# Main.net
KiCad netlist of a schematic drawn in Altium Designer
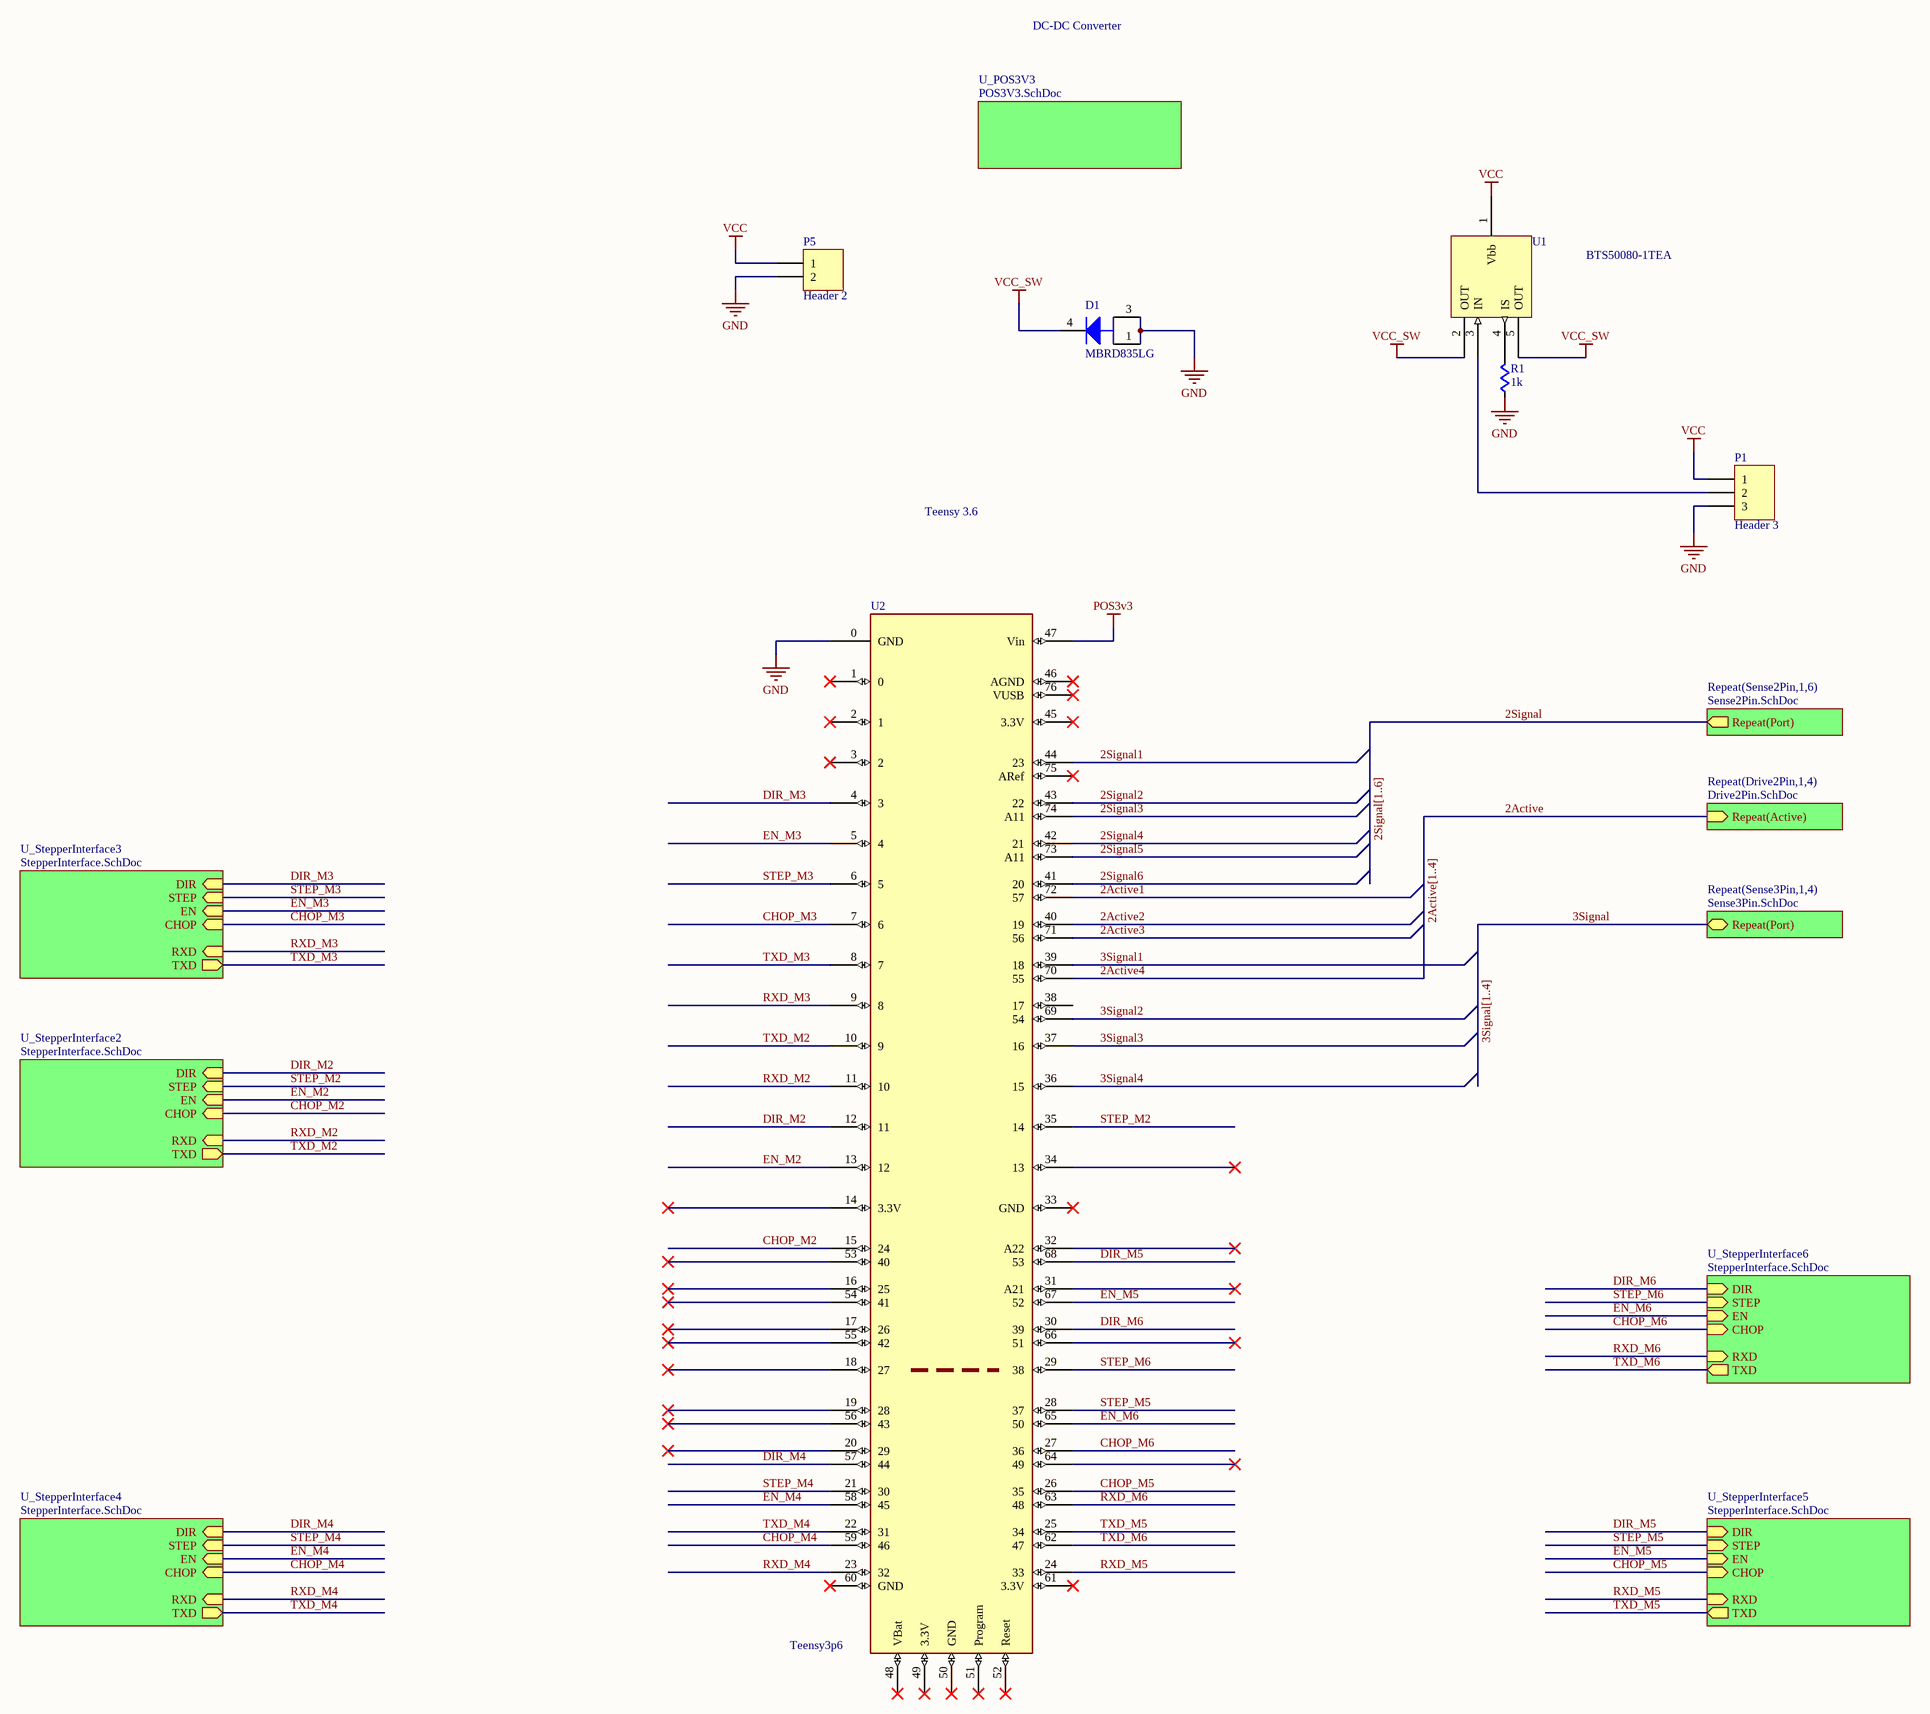
[diagram p0: Main.SchDoc]

(export (version "E")
  (design (tool "Eeschema 10.0.6"))
  (components
    (comp (ref "D1")
      (value "MBRD835LG")
      (footprint "ONSC-DPAK-3-369C-01_V")
      (description "SWITCHMODE(TM) Power Rectifier, 3-Pin DPAK, Pb-Free, Tube")
      (fields (field (name "MANUFACTURER") "On Semiconductor"))
      (libsource (lib "Altium Content Vault") (part "ONSC-D-A1A3K4-3_A"))
    )
    (comp (ref "P1")
      (value "Header 3")
      (footprint "HDR1X3")
      (description "Header, 3-Pin")
      (fields (field (name "PUBLISHER") "Altium Limited"))
      (libsource (lib "Miscellaneous Connectors") (part "Header 3"))
    )
    (comp (ref "P5")
      (value "Header 2")
      (footprint "HDR1X2")
      (description "Header, 2-Pin")
      (fields (field (name "PUBLISHER") "Altium Limited"))
      (libsource (lib "Miscellaneous Connectors") (part "Header 2"))
    )
    (comp (ref "R1")
      (value "1k")
      (footprint "R0805")
      (description "resistor")
      (fields (field (name "Comment") "Res"))
      (libsource (lib "ChipComponents") (part "Res"))
    )
    (comp (ref "U1")
      (value "BTS50080-1TEA")
      (footprint "BTS50080")
      (description "Smart High-Side Power Switch")
      (libsource (lib "AEVC-lib") (part "BTS50080-1TEA"))
    )
    (comp (ref "U2")
      (value "Teensy3p6")
      (footprint "Teensy3p6_full")
      (libsource (lib "AEVC-lib") (part "Teensy3p6"))
    )
  )
  (nets
    (net (code "2") (name "/2Active1") (class "Default")
      (node (ref "U2") (pin "72") (pinfunction "57_72") (pintype "bidirectional"))
    )
    (net (code "3") (name "/2Active2") (class "Default")
      (node (ref "U2") (pin "40") (pinfunction "19_40") (pintype "bidirectional"))
    )
    (net (code "4") (name "/2Active3") (class "Default")
      (node (ref "U2") (pin "71") (pinfunction "56_71") (pintype "bidirectional"))
    )
    (net (code "5") (name "/2Active4") (class "Default")
      (node (ref "U2") (pin "70") (pinfunction "55_70") (pintype "bidirectional"))
    )
    (net (code "8") (name "/2Signal1") (class "Default")
      (node (ref "U2") (pin "44") (pinfunction "23_44") (pintype "bidirectional"))
    )
    (net (code "9") (name "/2Signal2") (class "Default")
      (node (ref "U2") (pin "43") (pinfunction "22_43") (pintype "bidirectional"))
    )
    (net (code "10") (name "/2Signal3") (class "Default")
      (node (ref "U2") (pin "74") (pinfunction "A11_74") (pintype "bidirectional"))
    )
    (net (code "11") (name "/2Signal4") (class "Default")
      (node (ref "U2") (pin "42") (pinfunction "21_42") (pintype "bidirectional"))
    )
    (net (code "12") (name "/2Signal5") (class "Default")
      (node (ref "U2") (pin "73") (pinfunction "A11_73") (pintype "bidirectional"))
    )
    (net (code "13") (name "/2Signal6") (class "Default")
      (node (ref "U2") (pin "41") (pinfunction "20_41") (pintype "bidirectional"))
    )
    (net (code "16") (name "/3Signal1") (class "Default")
      (node (ref "U2") (pin "39") (pinfunction "18_39") (pintype "bidirectional"))
    )
    (net (code "17") (name "/3Signal2") (class "Default")
      (node (ref "U2") (pin "69") (pinfunction "54_69") (pintype "bidirectional"))
    )
    (net (code "18") (name "/3Signal3") (class "Default")
      (node (ref "U2") (pin "37") (pinfunction "16_37") (pintype "bidirectional"))
    )
    (net (code "19") (name "/3Signal4") (class "Default")
      (node (ref "U2") (pin "36") (pinfunction "15_36") (pintype "bidirectional"))
    )
    (net (code "21") (name "/CHOP_M2") (class "Default")
      (node (ref "U2") (pin "15") (pinfunction "24_15") (pintype "bidirectional"))
    )
    (net (code "22") (name "/CHOP_M3") (class "Default")
      (node (ref "U2") (pin "7") (pinfunction "6_7") (pintype "bidirectional"))
    )
    (net (code "23") (name "/CHOP_M4") (class "Default")
      (node (ref "U2") (pin "59") (pinfunction "46_59") (pintype "bidirectional"))
    )
    (net (code "24") (name "/CHOP_M5") (class "Default")
      (node (ref "U2") (pin "26") (pinfunction "35_26") (pintype "bidirectional"))
    )
    (net (code "25") (name "/CHOP_M6") (class "Default")
      (node (ref "U2") (pin "27") (pinfunction "36_27") (pintype "bidirectional"))
    )
    (net (code "26") (name "/DIR_M2") (class "Default")
      (node (ref "U2") (pin "12") (pinfunction "11_12") (pintype "bidirectional"))
    )
    (net (code "27") (name "/DIR_M3") (class "Default")
      (node (ref "U2") (pin "4") (pinfunction "3_4") (pintype "bidirectional"))
    )
    (net (code "28") (name "/DIR_M4") (class "Default")
      (node (ref "U2") (pin "57") (pinfunction "44_57") (pintype "bidirectional"))
    )
    (net (code "29") (name "/DIR_M5") (class "Default")
      (node (ref "U2") (pin "68") (pinfunction "53_68") (pintype "bidirectional"))
    )
    (net (code "30") (name "/DIR_M6") (class "Default")
      (node (ref "U2") (pin "30") (pinfunction "39_30") (pintype "bidirectional"))
    )
    (net (code "31") (name "/EN_M2") (class "Default")
      (node (ref "U2") (pin "13") (pinfunction "12_13") (pintype "bidirectional"))
    )
    (net (code "32") (name "/EN_M3") (class "Default")
      (node (ref "U2") (pin "5") (pinfunction "4_5") (pintype "bidirectional"))
    )
    (net (code "33") (name "/EN_M4") (class "Default")
      (node (ref "U2") (pin "58") (pinfunction "45_58") (pintype "bidirectional"))
    )
    (net (code "34") (name "/EN_M5") (class "Default")
      (node (ref "U2") (pin "67") (pinfunction "52_67") (pintype "bidirectional"))
    )
    (net (code "35") (name "/EN_M6") (class "Default")
      (node (ref "U2") (pin "65") (pinfunction "50_65") (pintype "bidirectional"))
    )
    (net (code "36") (name "/RXD_M2") (class "Default")
      (node (ref "U2") (pin "11") (pinfunction "10_11") (pintype "bidirectional"))
    )
    (net (code "37") (name "/RXD_M3") (class "Default")
      (node (ref "U2") (pin "9") (pinfunction "8_9") (pintype "bidirectional"))
    )
    (net (code "38") (name "/RXD_M4") (class "Default")
      (node (ref "U2") (pin "23") (pinfunction "32_23") (pintype "bidirectional"))
    )
    (net (code "39") (name "/RXD_M5") (class "Default")
      (node (ref "U2") (pin "24") (pinfunction "33_24") (pintype "bidirectional"))
    )
    (net (code "40") (name "/RXD_M6") (class "Default")
      (node (ref "U2") (pin "63") (pinfunction "48_63") (pintype "bidirectional"))
    )
    (net (code "41") (name "/STEP_M2") (class "Default")
      (node (ref "U2") (pin "35") (pinfunction "14_35") (pintype "bidirectional"))
    )
    (net (code "42") (name "/STEP_M3") (class "Default")
      (node (ref "U2") (pin "6") (pinfunction "5_6") (pintype "bidirectional"))
    )
    (net (code "43") (name "/STEP_M4") (class "Default")
      (node (ref "U2") (pin "21") (pinfunction "30_21") (pintype "bidirectional"))
    )
    (net (code "44") (name "/STEP_M5") (class "Default")
      (node (ref "U2") (pin "28") (pinfunction "37_28") (pintype "bidirectional"))
    )
    (net (code "45") (name "/STEP_M6") (class "Default")
      (node (ref "U2") (pin "29") (pinfunction "38_29") (pintype "bidirectional"))
    )
    (net (code "46") (name "/TXD_M2") (class "Default")
      (node (ref "U2") (pin "10") (pinfunction "9_10") (pintype "bidirectional"))
    )
    (net (code "47") (name "/TXD_M3") (class "Default")
      (node (ref "U2") (pin "8") (pinfunction "7_8") (pintype "bidirectional"))
    )
    (net (code "48") (name "/TXD_M4") (class "Default")
      (node (ref "U2") (pin "22") (pinfunction "31_22") (pintype "bidirectional"))
    )
    (net (code "49") (name "/TXD_M5") (class "Default")
      (node (ref "U2") (pin "25") (pinfunction "34_25") (pintype "bidirectional"))
    )
    (net (code "50") (name "/TXD_M6") (class "Default")
      (node (ref "U2") (pin "62") (pinfunction "47_62") (pintype "bidirectional"))
    )
    (net (code "51") (name "GND") (class "Default")
      (node (ref "D1") (pin "1") (pinfunction "A_1") (pintype "passive"))
      (node (ref "D1") (pin "3") (pinfunction "A_3") (pintype "passive"))
      (node (ref "P1") (pin "3") (pinfunction "3_3") (pintype "passive"))
      (node (ref "P5") (pin "2") (pinfunction "2_2") (pintype "passive"))
      (node (ref "R1") (pin "1") (pinfunction "1_1") (pintype "passive"))
      (node (ref "U2") (pin "0") (pinfunction "GND_0") (pintype "power_in"))
    )
    (net (code "52") (name "Net-(U1-IN)") (class "Default")
      (node (ref "P1") (pin "2") (pinfunction "2_2") (pintype "passive"))
      (node (ref "U1") (pin "3") (pinfunction "IN_3") (pintype "input"))
    )
    (net (code "53") (name "Net-(U1-IS)") (class "Default")
      (node (ref "R1") (pin "2") (pinfunction "2_2") (pintype "passive"))
      (node (ref "U1") (pin "4") (pinfunction "IS_4") (pintype "output"))
    )
    (net (code "54") (name "POS3v3") (class "Default")
      (node (ref "U2") (pin "47") (pinfunction "Vin_47") (pintype "bidirectional"))
    )
    (net (code "55") (name "VCC") (class "Default")
      (node (ref "P1") (pin "1") (pinfunction "1_1") (pintype "passive"))
      (node (ref "P5") (pin "1") (pinfunction "1_1") (pintype "passive"))
      (node (ref "U1") (pin "1") (pinfunction "Vbb_1") (pintype "power_in"))
    )
    (net (code "56") (name "VCC_SW") (class "Default")
      (node (ref "D1") (pin "4") (pinfunction "K_4") (pintype "passive"))
      (node (ref "U1") (pin "2") (pinfunction "OUT_2") (pintype "power_in"))
      (node (ref "U1") (pin "5") (pinfunction "OUT_5") (pintype "power_in"))
    )
    (net (code "57") (name "unconnected-(U2-0-Pad1)") (class "Default")
      (node (ref "U2") (pin "1") (pinfunction "0_1") (pintype "bidirectional+no_connect"))
    )
    (net (code "58") (name "unconnected-(U2-1-Pad2)") (class "Default")
      (node (ref "U2") (pin "2") (pinfunction "1_2") (pintype "bidirectional+no_connect"))
    )
    (net (code "59") (name "unconnected-(U2-2-Pad3)") (class "Default")
      (node (ref "U2") (pin "3") (pinfunction "2_3") (pintype "bidirectional+no_connect"))
    )
    (net (code "60") (name "unconnected-(U2-3.3V-Pad14)") (class "Default")
      (node (ref "U2") (pin "14") (pinfunction "3.3V_14") (pintype "bidirectional+no_connect"))
    )
    (net (code "61") (name "unconnected-(U2-3.3V-Pad45)") (class "Default")
      (node (ref "U2") (pin "45") (pinfunction "3.3V_45") (pintype "bidirectional+no_connect"))
    )
    (net (code "62") (name "unconnected-(U2-3.3V-Pad49)") (class "Default")
      (node (ref "U2") (pin "49") (pinfunction "3.3V_49") (pintype "bidirectional+no_connect"))
    )
    (net (code "63") (name "unconnected-(U2-3.3V-Pad61)") (class "Default")
      (node (ref "U2") (pin "61") (pinfunction "3.3V_61") (pintype "bidirectional+no_connect"))
    )
    (net (code "64") (name "unconnected-(U2-13-Pad34)") (class "Default")
      (node (ref "U2") (pin "34") (pinfunction "13_34") (pintype "bidirectional+no_connect"))
    )
    (net (code "65") (name "unconnected-(U2-17-Pad38)") (class "Default")
      (node (ref "U2") (pin "38") (pinfunction "17_38") (pintype "bidirectional"))
    )
    (net (code "66") (name "unconnected-(U2-25-Pad16)") (class "Default")
      (node (ref "U2") (pin "16") (pinfunction "25_16") (pintype "bidirectional+no_connect"))
    )
    (net (code "67") (name "unconnected-(U2-26-Pad17)") (class "Default")
      (node (ref "U2") (pin "17") (pinfunction "26_17") (pintype "bidirectional+no_connect"))
    )
    (net (code "68") (name "unconnected-(U2-27-Pad18)") (class "Default")
      (node (ref "U2") (pin "18") (pinfunction "27_18") (pintype "bidirectional+no_connect"))
    )
    (net (code "69") (name "unconnected-(U2-28-Pad19)") (class "Default")
      (node (ref "U2") (pin "19") (pinfunction "28_19") (pintype "bidirectional+no_connect"))
    )
    (net (code "70") (name "unconnected-(U2-29-Pad20)") (class "Default")
      (node (ref "U2") (pin "20") (pinfunction "29_20") (pintype "bidirectional+no_connect"))
    )
    (net (code "71") (name "unconnected-(U2-40-Pad53)") (class "Default")
      (node (ref "U2") (pin "53") (pinfunction "40_53") (pintype "bidirectional+no_connect"))
    )
    (net (code "72") (name "unconnected-(U2-41-Pad54)") (class "Default")
      (node (ref "U2") (pin "54") (pinfunction "41_54") (pintype "bidirectional+no_connect"))
    )
    (net (code "73") (name "unconnected-(U2-42-Pad55)") (class "Default")
      (node (ref "U2") (pin "55") (pinfunction "42_55") (pintype "bidirectional+no_connect"))
    )
    (net (code "74") (name "unconnected-(U2-43-Pad56)") (class "Default")
      (node (ref "U2") (pin "56") (pinfunction "43_56") (pintype "bidirectional+no_connect"))
    )
    (net (code "75") (name "unconnected-(U2-49-Pad64)") (class "Default")
      (node (ref "U2") (pin "64") (pinfunction "49_64") (pintype "bidirectional+no_connect"))
    )
    (net (code "76") (name "unconnected-(U2-51-Pad66)") (class "Default")
      (node (ref "U2") (pin "66") (pinfunction "51_66") (pintype "bidirectional+no_connect"))
    )
    (net (code "77") (name "unconnected-(U2-A21-Pad31)") (class "Default")
      (node (ref "U2") (pin "31") (pinfunction "A21_31") (pintype "bidirectional+no_connect"))
    )
    (net (code "78") (name "unconnected-(U2-A22-Pad32)") (class "Default")
      (node (ref "U2") (pin "32") (pinfunction "A22_32") (pintype "bidirectional+no_connect"))
    )
    (net (code "79") (name "unconnected-(U2-AGND-Pad46)") (class "Default")
      (node (ref "U2") (pin "46") (pinfunction "AGND_46") (pintype "bidirectional+no_connect"))
    )
    (net (code "80") (name "unconnected-(U2-ARef-Pad75)") (class "Default")
      (node (ref "U2") (pin "75") (pinfunction "ARef_75") (pintype "bidirectional+no_connect"))
    )
    (net (code "81") (name "unconnected-(U2-GND-Pad33)") (class "Default")
      (node (ref "U2") (pin "33") (pinfunction "GND_33") (pintype "bidirectional+no_connect"))
    )
    (net (code "82") (name "unconnected-(U2-GND-Pad50)") (class "Default")
      (node (ref "U2") (pin "50") (pinfunction "GND_50") (pintype "bidirectional+no_connect"))
    )
    (net (code "83") (name "unconnected-(U2-GND-Pad60)") (class "Default")
      (node (ref "U2") (pin "60") (pinfunction "GND_60") (pintype "bidirectional+no_connect"))
    )
    (net (code "84") (name "unconnected-(U2-Program-Pad51)") (class "Default")
      (node (ref "U2") (pin "51") (pinfunction "Program_51") (pintype "bidirectional+no_connect"))
    )
    (net (code "85") (name "unconnected-(U2-Reset-Pad52)") (class "Default")
      (node (ref "U2") (pin "52") (pinfunction "Reset_52") (pintype "bidirectional+no_connect"))
    )
    (net (code "86") (name "unconnected-(U2-VBat-Pad48)") (class "Default")
      (node (ref "U2") (pin "48") (pinfunction "VBat_48") (pintype "bidirectional+no_connect"))
    )
    (net (code "87") (name "unconnected-(U2-VUSB-Pad76)") (class "Default")
      (node (ref "U2") (pin "76") (pinfunction "VUSB_76") (pintype "bidirectional+no_connect"))
    )
  )
)
